# automotive-mirror-microcontroller-inline.net
KiCad netlist of a schematic drawn in Altium Designer
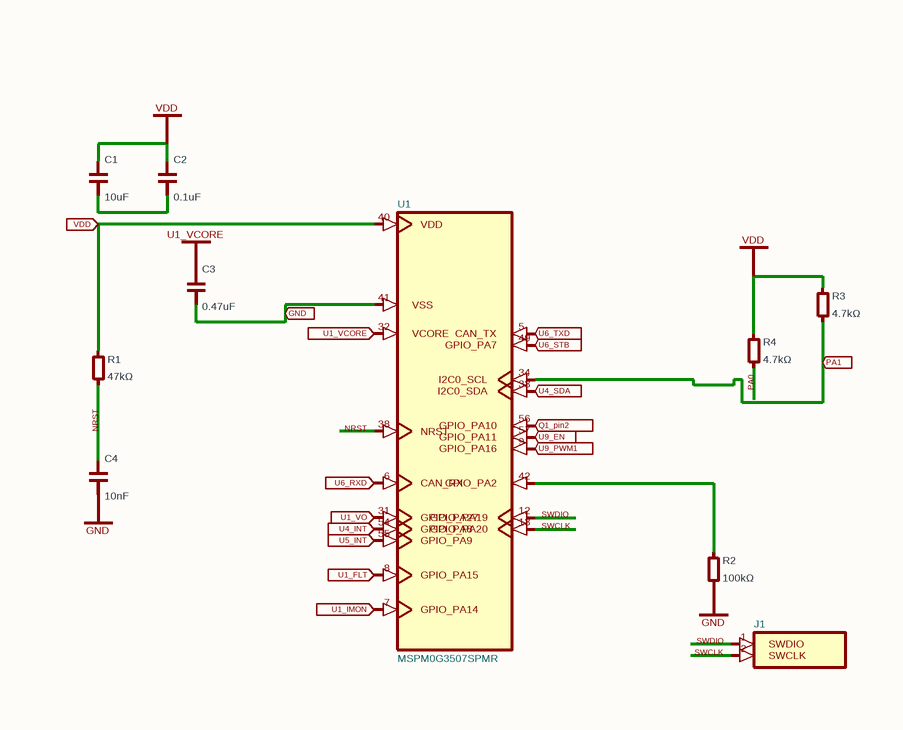
[diagram p0: automotive-mirror-microcontroller-inline-text-3pt.SchDoc]

(export (version "E")
  (design (tool "Eeschema 10.0.6"))
  (components
    (comp (ref "C1") (value "10uF") (libsource (lib "altium-import") (part "root_0_capacitor_down_")))
    (comp (ref "C2") (value "0.1uF") (libsource (lib "altium-import") (part "root_0_capacitor_down_")))
    (comp (ref "C3") (value "0.47uF") (libsource (lib "altium-import") (part "root_0_capacitor_down_")))
    (comp (ref "C4") (value "10nF") (libsource (lib "altium-import") (part "root_0_capacitor_down_")))
    (comp (ref "J1") (value "~") (libsource (lib "altium-import") (part "root_0_J1_")))
    (comp (ref "R1") (value "47kΩ") (libsource (lib "altium-import") (part "root_0_boxresistor_up_")))
    (comp (ref "R2") (value "100kΩ") (libsource (lib "altium-import") (part "root_0_boxresistor_down_")))
    (comp (ref "R3") (value "4.7kΩ") (libsource (lib "altium-import") (part "root_0_boxresistor_up_")))
    (comp (ref "R4") (value "4.7kΩ") (libsource (lib "altium-import") (part "root_0_boxresistor_up_")))
    (comp (ref "U1") (value "~") (libsource (lib "altium-import") (part "root_0_U1_")))
  )
  (nets
    (net (code "1") (name "/PA1") (class "Default")
      (node (ref "R3") (pin "1") (pinfunction "anode_1") (pintype "input"))
      (node (ref "U1") (pin "34") (pinfunction "I2C0_SCL_34") (pintype "input"))
    )
    (net (code "2") (name "/Q1_pin2") (class "Default")
      (node (ref "U1") (pin "56") (pinfunction "GPIO_PA10_56") (pintype "input"))
    )
    (net (code "3") (name "/U1_FLT") (class "Default")
      (node (ref "U1") (pin "8") (pinfunction "GPIO_PA15_8") (pintype "input"))
    )
    (net (code "4") (name "/U1_IMON") (class "Default")
      (node (ref "U1") (pin "7") (pinfunction "GPIO_PA14_7") (pintype "input"))
    )
    (net (code "5") (name "/U1_VO") (class "Default")
      (node (ref "U1") (pin "31") (pinfunction "GPIO_PA27_31") (pintype "input"))
    )
    (net (code "6") (name "/U4_INT") (class "Default")
      (node (ref "U1") (pin "54") (pinfunction "GPIO_PA8_54") (pintype "input"))
    )
    (net (code "7") (name "/U4_SDA") (class "Default")
      (node (ref "U1") (pin "33") (pinfunction "I2C0_SDA_33") (pintype "input"))
    )
    (net (code "8") (name "/U5_INT") (class "Default")
      (node (ref "U1") (pin "55") (pinfunction "GPIO_PA9_55") (pintype "input"))
    )
    (net (code "9") (name "/U6_RXD") (class "Default")
      (node (ref "U1") (pin "6") (pinfunction "CAN_RX_6") (pintype "input"))
    )
    (net (code "10") (name "/U6_STB") (class "Default")
      (node (ref "U1") (pin "49") (pinfunction "GPIO_PA7_49") (pintype "input"))
    )
    (net (code "11") (name "/U6_TXD") (class "Default")
      (node (ref "U1") (pin "5") (pinfunction "CAN_TX_5") (pintype "input"))
    )
    (net (code "12") (name "/U9_EN") (class "Default")
      (node (ref "U1") (pin "57") (pinfunction "GPIO_PA11_57") (pintype "input"))
    )
    (net (code "13") (name "/U9_PWM1") (class "Default")
      (node (ref "U1") (pin "9") (pinfunction "GPIO_PA16_9") (pintype "input"))
    )
    (net (code "14") (name "GND") (class "Default")
      (node (ref "C3") (pin "2") (pinfunction "cathode_2") (pintype "input"))
      (node (ref "C4") (pin "2") (pinfunction "cathode_2") (pintype "input"))
      (node (ref "R2") (pin "2") (pinfunction "cathode_2") (pintype "input"))
      (node (ref "U1") (pin "41") (pinfunction "VSS_41") (pintype "input"))
    )
    (net (code "15") (name "Net-(C1-cathode)") (class "Default")
      (node (ref "C1") (pin "2") (pinfunction "cathode_2") (pintype "input"))
      (node (ref "C2") (pin "2") (pinfunction "cathode_2") (pintype "input"))
    )
    (net (code "16") (name "Net-(C4-anode)") (class "Default")
      (node (ref "C4") (pin "1") (pinfunction "anode_1") (pintype "input"))
      (node (ref "R1") (pin "1") (pinfunction "anode_1") (pintype "input"))
    )
    (net (code "17") (name "Net-(R2-anode)") (class "Default")
      (node (ref "R2") (pin "1") (pinfunction "anode_1") (pintype "input"))
      (node (ref "U1") (pin "42") (pinfunction "GPIO_PA2_42") (pintype "input"))
    )
    (net (code "18") (name "U1_VCORE") (class "Default")
      (node (ref "C3") (pin "1") (pinfunction "anode_1") (pintype "input"))
      (node (ref "U1") (pin "32") (pinfunction "VCORE_32") (pintype "input"))
    )
    (net (code "19") (name "VDD") (class "Default")
      (node (ref "C1") (pin "1") (pinfunction "anode_1") (pintype "input"))
      (node (ref "C2") (pin "1") (pinfunction "anode_1") (pintype "input"))
      (node (ref "R1") (pin "2") (pinfunction "cathode_2") (pintype "input"))
      (node (ref "R3") (pin "2") (pinfunction "cathode_2") (pintype "input"))
      (node (ref "R4") (pin "2") (pinfunction "cathode_2") (pintype "input"))
      (node (ref "U1") (pin "40") (pinfunction "VDD_40") (pintype "input"))
    )
    (net (code "20") (name "unconnected-(J1-SWCLK-Pad2)") (class "Default")
      (node (ref "J1") (pin "2") (pinfunction "SWCLK_2") (pintype "input"))
    )
    (net (code "21") (name "unconnected-(J1-SWDIO-Pad1)") (class "Default")
      (node (ref "J1") (pin "1") (pinfunction "SWDIO_1") (pintype "input"))
    )
    (net (code "22") (name "unconnected-(R4-anode-Pad1)") (class "Default")
      (node (ref "R4") (pin "1") (pinfunction "anode_1") (pintype "input"))
    )
    (net (code "23") (name "unconnected-(U1-GPIO_PA19-Pad12)") (class "Default")
      (node (ref "U1") (pin "12") (pinfunction "GPIO_PA19_12") (pintype "input"))
    )
    (net (code "24") (name "unconnected-(U1-GPIO_PA20-Pad13)") (class "Default")
      (node (ref "U1") (pin "13") (pinfunction "GPIO_PA20_13") (pintype "input"))
    )
    (net (code "25") (name "unconnected-(U1-NRST-Pad38)") (class "Default")
      (node (ref "U1") (pin "38") (pinfunction "NRST_38") (pintype "input"))
    )
  )
)
